# SoC_SDIO.net
KiCad netlist of a schematic drawn in Altium Designer
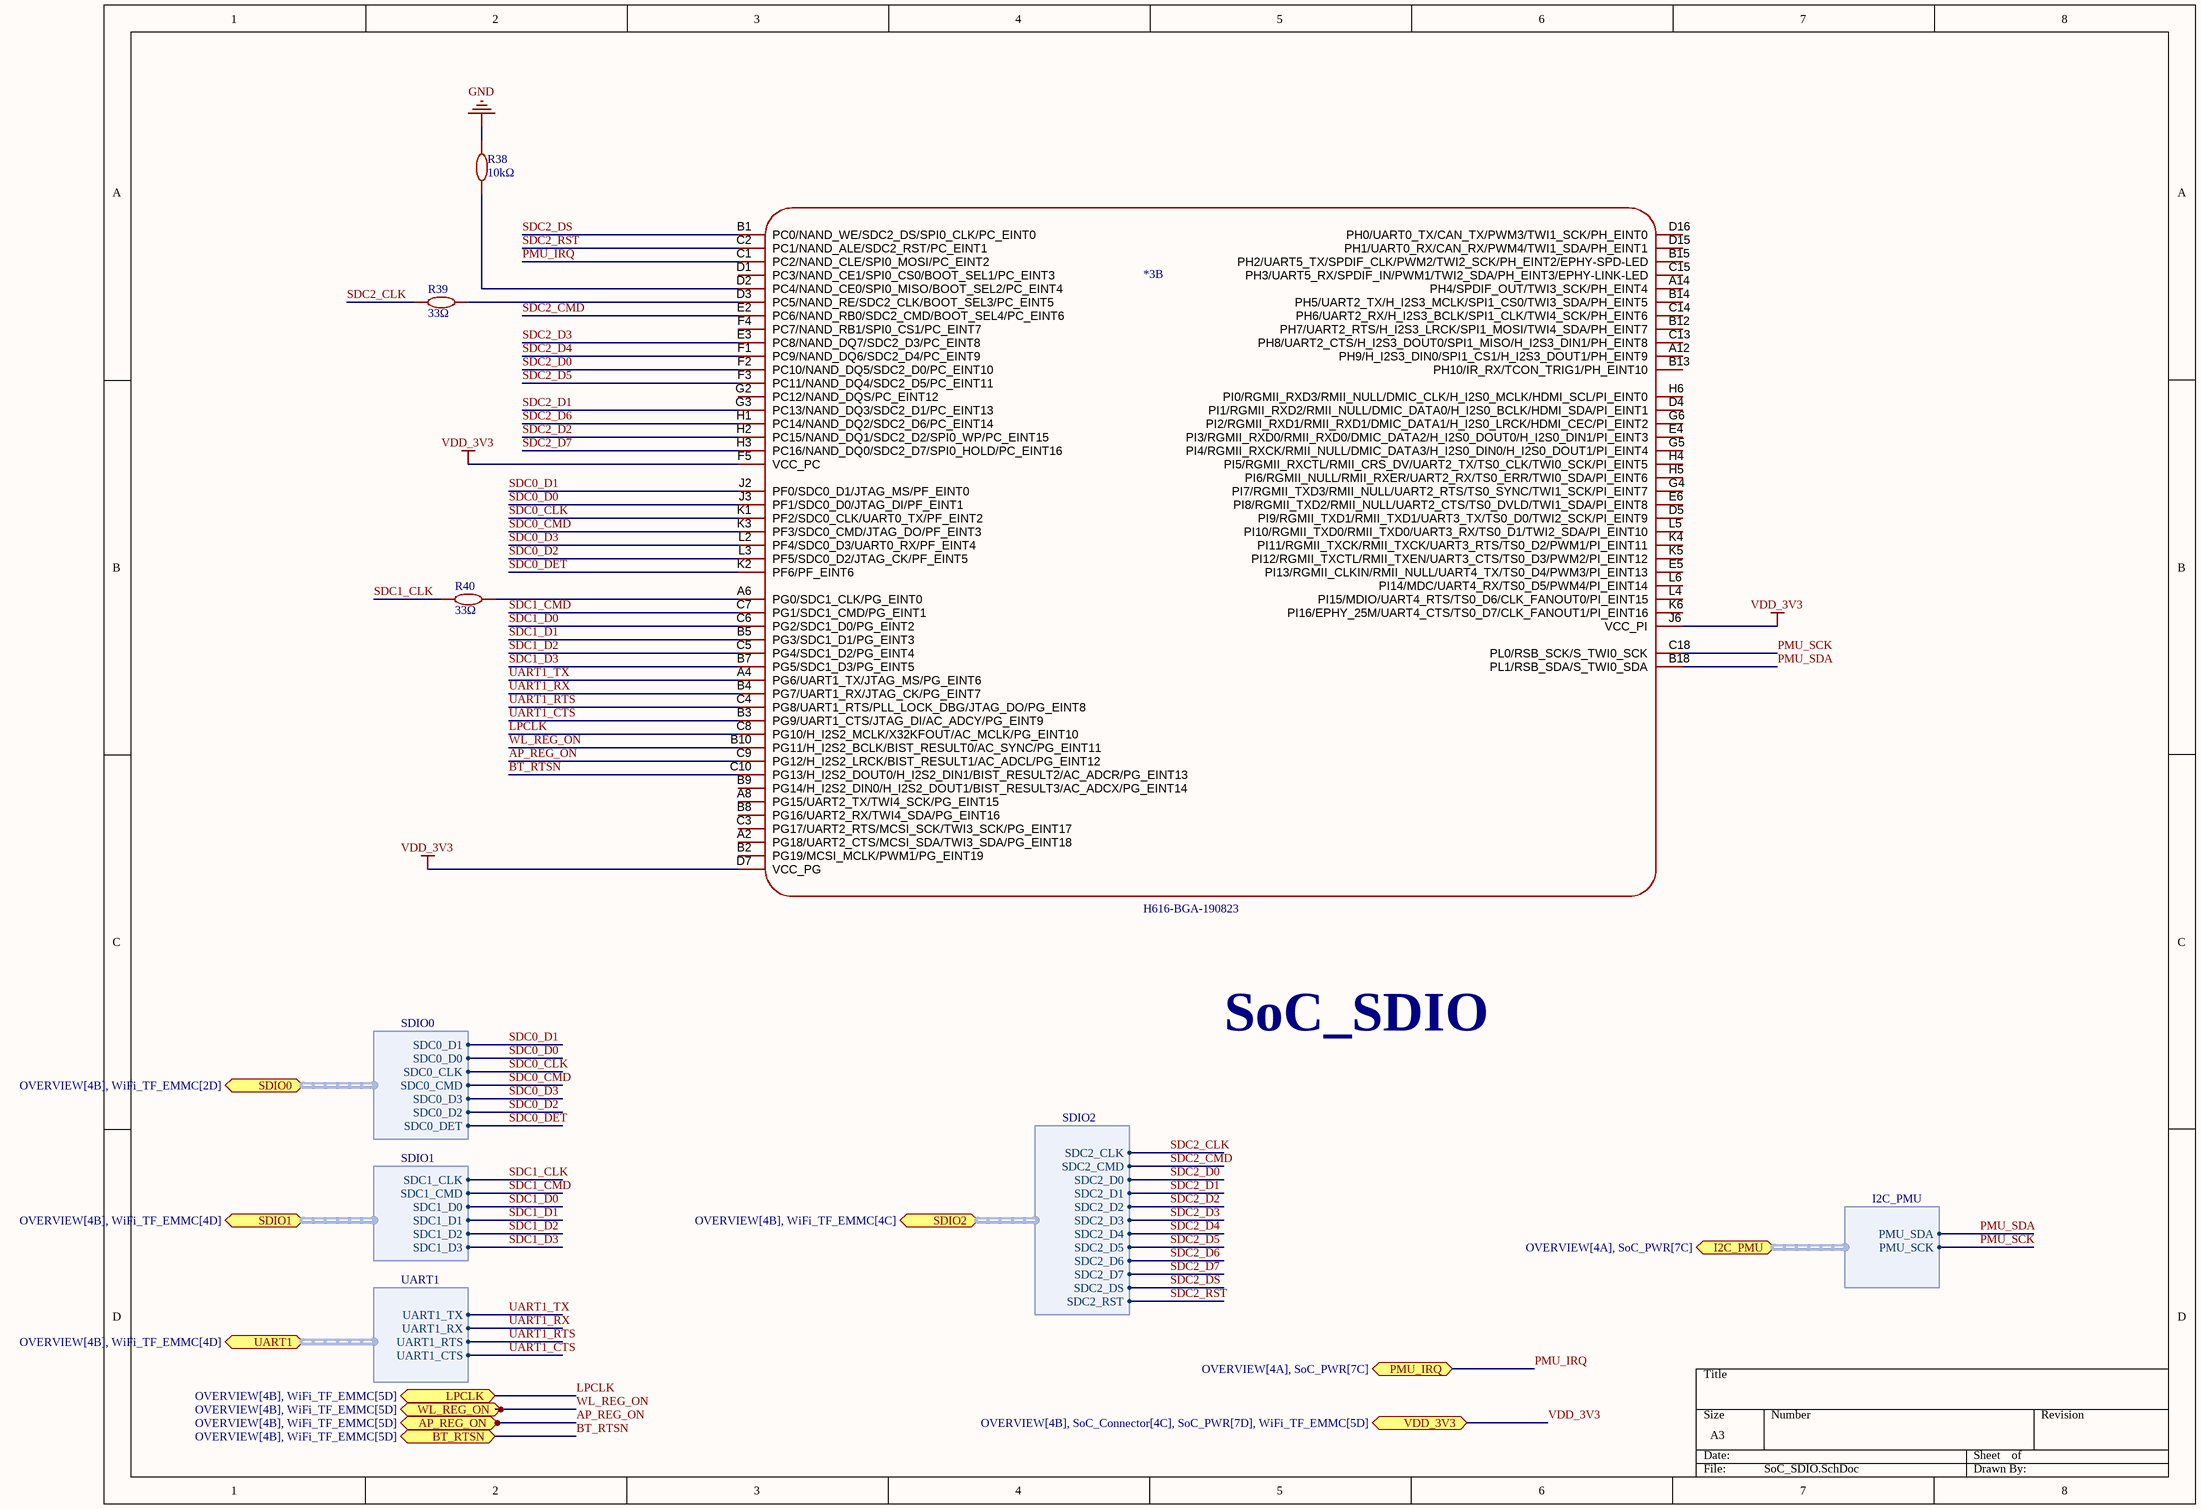
[diagram p0: SoC_SDIO.SchDoc]

(export (version "E")
  (design (tool "Eeschema 10.0.6"))
  (components
    (comp (ref "*3")
      (value "H616-BGA-190823")
      (footprint "BGA-284_L14.0-W12.0-P0.65-TL")
      (description "Allwinner H616")
      (libsource (lib "IC") (part "H616-BGA-190823"))
    )
    (comp (ref "R38")
      (value "10kΩ")
      (footprint "R0402")
      (description "62.5mW 10kΩ 50V ±100ppm/℃ Thick Film Resistor ±1% 0402 Chip Resistor - Surface Mount ROHS")
      (libsource (lib "RLC") (part "10kΩ"))
    )
    (comp (ref "R39")
      (value "33Ω")
      (footprint "R0402")
      (description "62.5mW 33Ω 50V ±100ppm/℃ Thick Film Resistor ±1% 0402 Chip Resistor - Surface Mount ROHS")
      (libsource (lib "RLC") (part "33Ω"))
    )
    (comp (ref "R40")
      (value "33Ω")
      (footprint "R0402")
      (description "62.5mW 33Ω 50V ±100ppm/℃ Thick Film Resistor ±1% 0402 Chip Resistor - Surface Mount ROHS")
      (libsource (lib "RLC") (part "33Ω"))
    )
  )
  (nets
    (net (code "6") (name "/AP_REG_ON") (class "Default")
      (node (ref "*3") (pin "C9") (pinfunction "PG12/H_I2S2_LRCK/BIST_RESULT1/AC_ADCL/PG_EINT12_C9") (pintype "passive"))
    )
    (net (code "7") (name "/BT_RTSN") (class "Default")
      (node (ref "*3") (pin "C10") (pinfunction "PG13/H_I2S2_DOUT0/H_I2S2_DIN1/BIST_RESULT2/AC_ADCR/PG_EINT13_C10") (pintype "passive"))
    )
    (net (code "8") (name "/LPCLK") (class "Default")
      (node (ref "*3") (pin "C8") (pinfunction "PG10/H_I2S2_MCLK/X32KFOUT/AC_MCLK/PG_EINT10_C8") (pintype "passive"))
    )
    (net (code "9") (name "/PMU_IRQ") (class "Default")
      (node (ref "*3") (pin "C1") (pinfunction "PC2/NAND_CLE/SPI0_MOSI/PC_EINT2_C1") (pintype "passive"))
    )
    (net (code "10") (name "/PMU_SCK") (class "Default")
      (node (ref "*3") (pin "C18") (pinfunction "PL0/RSB_SCK/S_TWI0_SCK_C18") (pintype "passive"))
    )
    (net (code "11") (name "/PMU_SDA") (class "Default")
      (node (ref "*3") (pin "B18") (pinfunction "PL1/RSB_SDA/S_TWI0_SDA_B18") (pintype "passive"))
    )
    (net (code "12") (name "/SDC0_CLK") (class "Default")
      (node (ref "*3") (pin "K1") (pinfunction "PF2/SDC0_CLK/UART0_TX/PF_EINT2_K1") (pintype "passive"))
    )
    (net (code "13") (name "/SDC0_CMD") (class "Default")
      (node (ref "*3") (pin "K3") (pinfunction "PF3/SDC0_CMD/JTAG_DO/PF_EINT3_K3") (pintype "passive"))
    )
    (net (code "14") (name "/SDC0_D0") (class "Default")
      (node (ref "*3") (pin "J3") (pinfunction "PF1/SDC0_D0/JTAG_DI/PF_EINT1_J3") (pintype "passive"))
    )
    (net (code "15") (name "/SDC0_D1") (class "Default")
      (node (ref "*3") (pin "J2") (pinfunction "PF0/SDC0_D1/JTAG_MS/PF_EINT0_J2") (pintype "passive"))
    )
    (net (code "16") (name "/SDC0_D2") (class "Default")
      (node (ref "*3") (pin "L3") (pinfunction "PF5/SDC0_D2/JTAG_CK/PF_EINT5_L3") (pintype "passive"))
    )
    (net (code "17") (name "/SDC0_D3") (class "Default")
      (node (ref "*3") (pin "L2") (pinfunction "PF4/SDC0_D3/UART0_RX/PF_EINT4_L2") (pintype "passive"))
    )
    (net (code "18") (name "/SDC0_DET") (class "Default")
      (node (ref "*3") (pin "K2") (pinfunction "PF6/PF_EINT6_K2") (pintype "passive"))
    )
    (net (code "19") (name "/SDC1_CLK") (class "Default")
      (node (ref "R40") (pin "1") (pinfunction "1_1") (pintype "passive"))
    )
    (net (code "20") (name "/SDC1_CMD") (class "Default")
      (node (ref "*3") (pin "C7") (pinfunction "PG1/SDC1_CMD/PG_EINT1_C7") (pintype "passive"))
    )
    (net (code "21") (name "/SDC1_D0") (class "Default")
      (node (ref "*3") (pin "C6") (pinfunction "PG2/SDC1_D0/PG_EINT2_C6") (pintype "passive"))
    )
    (net (code "22") (name "/SDC1_D1") (class "Default")
      (node (ref "*3") (pin "B5") (pinfunction "PG3/SDC1_D1/PG_EINT3_B5") (pintype "passive"))
    )
    (net (code "23") (name "/SDC1_D2") (class "Default")
      (node (ref "*3") (pin "C5") (pinfunction "PG4/SDC1_D2/PG_EINT4_C5") (pintype "passive"))
    )
    (net (code "24") (name "/SDC1_D3") (class "Default")
      (node (ref "*3") (pin "B7") (pinfunction "PG5/SDC1_D3/PG_EINT5_B7") (pintype "passive"))
    )
    (net (code "25") (name "/SDC2_CLK") (class "Default")
      (node (ref "R39") (pin "1") (pinfunction "1_1") (pintype "passive"))
    )
    (net (code "26") (name "/SDC2_CMD") (class "Default")
      (node (ref "*3") (pin "E2") (pinfunction "PC6/NAND_RB0/SDC2_CMD/BOOT_SEL4/PC_EINT6_E2") (pintype "passive"))
    )
    (net (code "27") (name "/SDC2_D0") (class "Default")
      (node (ref "*3") (pin "F2") (pinfunction "PC10/NAND_DQ5/SDC2_D0/PC_EINT10_F2") (pintype "passive"))
    )
    (net (code "28") (name "/SDC2_D1") (class "Default")
      (node (ref "*3") (pin "G3") (pinfunction "PC13/NAND_DQ3/SDC2_D1/PC_EINT13_G3") (pintype "passive"))
    )
    (net (code "29") (name "/SDC2_D2") (class "Default")
      (node (ref "*3") (pin "H2") (pinfunction "PC15/NAND_DQ1/SDC2_D2/SPI0_WP/PC_EINT15_H2") (pintype "passive"))
    )
    (net (code "30") (name "/SDC2_D3") (class "Default")
      (node (ref "*3") (pin "E3") (pinfunction "PC8/NAND_DQ7/SDC2_D3/PC_EINT8_E3") (pintype "passive"))
    )
    (net (code "31") (name "/SDC2_D4") (class "Default")
      (node (ref "*3") (pin "F1") (pinfunction "PC9/NAND_DQ6/SDC2_D4/PC_EINT9_F1") (pintype "passive"))
    )
    (net (code "32") (name "/SDC2_D5") (class "Default")
      (node (ref "*3") (pin "F3") (pinfunction "PC11/NAND_DQ4/SDC2_D5/PC_EINT11_F3") (pintype "passive"))
    )
    (net (code "33") (name "/SDC2_D6") (class "Default")
      (node (ref "*3") (pin "H1") (pinfunction "PC14/NAND_DQ2/SDC2_D6/PC_EINT14_H1") (pintype "passive"))
    )
    (net (code "34") (name "/SDC2_D7") (class "Default")
      (node (ref "*3") (pin "H3") (pinfunction "PC16/NAND_DQ0/SDC2_D7/SPI0_HOLD/PC_EINT16_H3") (pintype "passive"))
    )
    (net (code "35") (name "/SDC2_DS") (class "Default")
      (node (ref "*3") (pin "B1") (pinfunction "PC0/NAND_WE/SDC2_DS/SPI0_CLK/PC_EINT0_B1") (pintype "passive"))
    )
    (net (code "36") (name "/SDC2_RST") (class "Default")
      (node (ref "*3") (pin "C2") (pinfunction "PC1/NAND_ALE/SDC2_RST/PC_EINT1_C2") (pintype "passive"))
    )
    (net (code "37") (name "/UART1_CTS") (class "Default")
      (node (ref "*3") (pin "B3") (pinfunction "PG9/UART1_CTS/JTAG_DI/AC_ADCY/PG_EINT9_B3") (pintype "passive"))
    )
    (net (code "38") (name "/UART1_RTS") (class "Default")
      (node (ref "*3") (pin "C4") (pinfunction "PG8/UART1_RTS/PLL_LOCK_DBG/JTAG_DO/PG_EINT8_C4") (pintype "passive"))
    )
    (net (code "39") (name "/UART1_RX") (class "Default")
      (node (ref "*3") (pin "B4") (pinfunction "PG7/UART1_RX/JTAG_CK/PG_EINT7_B4") (pintype "passive"))
    )
    (net (code "40") (name "/UART1_TX") (class "Default")
      (node (ref "*3") (pin "A4") (pinfunction "PG6/UART1_TX/JTAG_MS/PG_EINT6_A4") (pintype "passive"))
    )
    (net (code "41") (name "/WL_REG_ON") (class "Default")
      (node (ref "*3") (pin "B10") (pinfunction "PG11/H_I2S2_BCLK/BIST_RESULT0/AC_SYNC/PG_EINT11_B10") (pintype "passive"))
    )
    (net (code "47") (name "GND") (class "Default")
      (node (ref "R38") (pin "2") (pinfunction "2_2") (pintype "passive"))
    )
    (net (code "48") (name "Net-(*3B-PC4{slash}NAND_CE0{slash}SPI0_MISO{slash}BOOT_SEL2{slash}PC_EINT4)") (class "Default")
      (node (ref "*3") (pin "D2") (pinfunction "PC4/NAND_CE0/SPI0_MISO/BOOT_SEL2/PC_EINT4_D2") (pintype "passive"))
      (node (ref "R38") (pin "1") (pinfunction "1_1") (pintype "passive"))
    )
    (net (code "49") (name "Net-(*3B-PC5{slash}NAND_RE{slash}SDC2_CLK{slash}BOOT_SEL3{slash}PC_EINT5)") (class "Default")
      (node (ref "*3") (pin "D3") (pinfunction "PC5/NAND_RE/SDC2_CLK/BOOT_SEL3/PC_EINT5_D3") (pintype "passive"))
      (node (ref "R39") (pin "2") (pinfunction "2_2") (pintype "passive"))
    )
    (net (code "50") (name "Net-(*3B-PG0{slash}SDC1_CLK{slash}PG_EINT0)") (class "Default")
      (node (ref "*3") (pin "A6") (pinfunction "PG0/SDC1_CLK/PG_EINT0_A6") (pintype "passive"))
      (node (ref "R40") (pin "2") (pinfunction "2_2") (pintype "passive"))
    )
    (net (code "51") (name "VDD_3V3") (class "Default")
      (node (ref "*3") (pin "D7") (pinfunction "VCC_PG_D7") (pintype "passive"))
      (node (ref "*3") (pin "F5") (pinfunction "VCC_PC_F5") (pintype "passive"))
      (node (ref "*3") (pin "J6") (pinfunction "VCC_PI_J6") (pintype "passive"))
    )
    (net (code "52") (name "unconnected-(*3B-PC3{slash}NAND_CE1{slash}SPI0_CS0{slash}BOOT_SEL1{slash}PC_EINT3-PadD1)") (class "Default")
      (node (ref "*3") (pin "D1") (pinfunction "PC3/NAND_CE1/SPI0_CS0/BOOT_SEL1/PC_EINT3_D1") (pintype "passive"))
    )
    (net (code "53") (name "unconnected-(*3B-PC7{slash}NAND_RB1{slash}SPI0_CS1{slash}PC_EINT7-PadF4)") (class "Default")
      (node (ref "*3") (pin "F4") (pinfunction "PC7/NAND_RB1/SPI0_CS1/PC_EINT7_F4") (pintype "passive"))
    )
    (net (code "54") (name "unconnected-(*3B-PC12{slash}NAND_DQS{slash}PC_EINT12-PadG2)") (class "Default")
      (node (ref "*3") (pin "G2") (pinfunction "PC12/NAND_DQS/PC_EINT12_G2") (pintype "passive"))
    )
    (net (code "55") (name "unconnected-(*3B-PG14{slash}H_I2S2_DIN0{slash}H_I2S2_DOUT1{slash}BIST_RESULT3{slash}AC_ADCX{slash}PG_EINT14-PadB9)") (class "Default")
      (node (ref "*3") (pin "B9") (pinfunction "PG14/H_I2S2_DIN0/H_I2S2_DOUT1/BIST_RESULT3/AC_ADCX/PG_EINT14_B9") (pintype "passive"))
    )
    (net (code "56") (name "unconnected-(*3B-PG15{slash}UART2_TX{slash}TWI4_SCK{slash}PG_EINT15-PadA8)") (class "Default")
      (node (ref "*3") (pin "A8") (pinfunction "PG15/UART2_TX/TWI4_SCK/PG_EINT15_A8") (pintype "passive"))
    )
    (net (code "57") (name "unconnected-(*3B-PG16{slash}UART2_RX{slash}TWI4_SDA{slash}PG_EINT16-PadB8)") (class "Default")
      (node (ref "*3") (pin "B8") (pinfunction "PG16/UART2_RX/TWI4_SDA/PG_EINT16_B8") (pintype "passive"))
    )
    (net (code "58") (name "unconnected-(*3B-PG17{slash}UART2_RTS{slash}MCSI_SCK{slash}TWI3_SCK{slash}PG_EINT17-PadC3)") (class "Default")
      (node (ref "*3") (pin "C3") (pinfunction "PG17/UART2_RTS/MCSI_SCK/TWI3_SCK/PG_EINT17_C3") (pintype "passive"))
    )
    (net (code "59") (name "unconnected-(*3B-PG18{slash}UART2_CTS{slash}MCSI_SDA{slash}TWI3_SDA{slash}PG_EINT18-PadA2)") (class "Default")
      (node (ref "*3") (pin "A2") (pinfunction "PG18/UART2_CTS/MCSI_SDA/TWI3_SDA/PG_EINT18_A2") (pintype "passive"))
    )
    (net (code "60") (name "unconnected-(*3B-PG19{slash}MCSI_MCLK{slash}PWM1{slash}PG_EINT19-PadB2)") (class "Default")
      (node (ref "*3") (pin "B2") (pinfunction "PG19/MCSI_MCLK/PWM1/PG_EINT19_B2") (pintype "passive"))
    )
    (net (code "61") (name "unconnected-(*3B-PH0{slash}UART0_TX{slash}CAN_TX{slash}PWM3{slash}TWI1_SCK{slash}PH_EINT0-PadD16)") (class "Default")
      (node (ref "*3") (pin "D16") (pinfunction "PH0/UART0_TX/CAN_TX/PWM3/TWI1_SCK/PH_EINT0_D16") (pintype "passive"))
    )
    (net (code "62") (name "unconnected-(*3B-PH1{slash}UART0_RX{slash}CAN_RX{slash}PWM4{slash}TWI1_SDA{slash}PH_EINT1-PadD15)") (class "Default")
      (node (ref "*3") (pin "D15") (pinfunction "PH1/UART0_RX/CAN_RX/PWM4/TWI1_SDA/PH_EINT1_D15") (pintype "passive"))
    )
    (net (code "63") (name "unconnected-(*3B-PH2{slash}UART5_TX{slash}SPDIF_CLK{slash}PWM2{slash}TWI2_SCK{slash}PH_EINT2{slash}EPHY-SPD-LED-PadB15)") (class "Default")
      (node (ref "*3") (pin "B15") (pinfunction "PH2/UART5_TX/SPDIF_CLK/PWM2/TWI2_SCK/PH_EINT2/EPHY-SPD-LED_B15") (pintype "passive"))
    )
    (net (code "64") (name "unconnected-(*3B-PH3{slash}UART5_RX{slash}SPDIF_IN{slash}PWM1{slash}TWI2_SDA{slash}PH_EINT3{slash}EPHY-LINK-LED-PadC15)") (class "Default")
      (node (ref "*3") (pin "C15") (pinfunction "PH3/UART5_RX/SPDIF_IN/PWM1/TWI2_SDA/PH_EINT3/EPHY-LINK-LED_C15") (pintype "passive"))
    )
    (net (code "65") (name "unconnected-(*3B-PH4{slash}SPDIF_OUT{slash}TWI3_SCK{slash}PH_EINT4-PadA14)") (class "Default")
      (node (ref "*3") (pin "A14") (pinfunction "PH4/SPDIF_OUT/TWI3_SCK/PH_EINT4_A14") (pintype "passive"))
    )
    (net (code "66") (name "unconnected-(*3B-PH5{slash}UART2_TX{slash}H_I2S3_MCLK{slash}SPI1_CS0{slash}TWI3_SDA{slash}PH_EINT5-PadB14)") (class "Default")
      (node (ref "*3") (pin "B14") (pinfunction "PH5/UART2_TX/H_I2S3_MCLK/SPI1_CS0/TWI3_SDA/PH_EINT5_B14") (pintype "passive"))
    )
    (net (code "67") (name "unconnected-(*3B-PH6{slash}UART2_RX{slash}H_I2S3_BCLK{slash}SPI1_CLK{slash}TWI4_SCK{slash}PH_EINT6-PadC14)") (class "Default")
      (node (ref "*3") (pin "C14") (pinfunction "PH6/UART2_RX/H_I2S3_BCLK/SPI1_CLK/TWI4_SCK/PH_EINT6_C14") (pintype "passive"))
    )
    (net (code "68") (name "unconnected-(*3B-PH7{slash}UART2_RTS{slash}H_I2S3_LRCK{slash}SPI1_MOSI{slash}TWI4_SDA{slash}PH_EINT7-PadB12)") (class "Default")
      (node (ref "*3") (pin "B12") (pinfunction "PH7/UART2_RTS/H_I2S3_LRCK/SPI1_MOSI/TWI4_SDA/PH_EINT7_B12") (pintype "passive"))
    )
    (net (code "69") (name "unconnected-(*3B-PH8{slash}UART2_CTS{slash}H_I2S3_DOUT0{slash}SPI1_MISO{slash}H_I2S3_DIN1{slash}PH_EINT8-PadC13)") (class "Default")
      (node (ref "*3") (pin "C13") (pinfunction "PH8/UART2_CTS/H_I2S3_DOUT0/SPI1_MISO/H_I2S3_DIN1/PH_EINT8_C13") (pintype "passive"))
    )
    (net (code "70") (name "unconnected-(*3B-PH9{slash}H_I2S3_DIN0{slash}SPI1_CS1{slash}H_I2S3_DOUT1{slash}PH_EINT9-PadA12)") (class "Default")
      (node (ref "*3") (pin "A12") (pinfunction "PH9/H_I2S3_DIN0/SPI1_CS1/H_I2S3_DOUT1/PH_EINT9_A12") (pintype "passive"))
    )
    (net (code "71") (name "unconnected-(*3B-PH10{slash}IR_RX{slash}TCON_TRIG1{slash}PH_EINT10-PadB13)") (class "Default")
      (node (ref "*3") (pin "B13") (pinfunction "PH10/IR_RX/TCON_TRIG1/PH_EINT10_B13") (pintype "passive"))
    )
    (net (code "72") (name "unconnected-(*3B-PI0{slash}RGMII_RXD3{slash}RMII_NULL{slash}DMIC_CLK{slash}H_I2S0_MCLK{slash}HDMI_SCL{slash}PI_EINT0-PadH6)") (class "Default")
      (node (ref "*3") (pin "H6") (pinfunction "PI0/RGMII_RXD3/RMII_NULL/DMIC_CLK/H_I2S0_MCLK/HDMI_SCL/PI_EINT0_H6") (pintype "passive"))
    )
    (net (code "73") (name "unconnected-(*3B-PI1{slash}RGMII_RXD2{slash}RMII_NULL{slash}DMIC_DATA0{slash}H_I2S0_BCLK{slash}HDMI_SDA{slash}PI_EINT1-PadD4)") (class "Default")
      (node (ref "*3") (pin "D4") (pinfunction "PI1/RGMII_RXD2/RMII_NULL/DMIC_DATA0/H_I2S0_BCLK/HDMI_SDA/PI_EINT1_D4") (pintype "passive"))
    )
    (net (code "74") (name "unconnected-(*3B-PI2{slash}RGMII_RXD1{slash}RMII_RXD1{slash}DMIC_DATA1{slash}H_I2S0_LRCK{slash}HDMI_CEC{slash}PI_EINT2-PadG6)") (class "Default")
      (node (ref "*3") (pin "G6") (pinfunction "PI2/RGMII_RXD1/RMII_RXD1/DMIC_DATA1/H_I2S0_LRCK/HDMI_CEC/PI_EINT2_G6") (pintype "passive"))
    )
    (net (code "75") (name "unconnected-(*3B-PI3{slash}RGMII_RXD0{slash}RMII_RXD0{slash}DMIC_DATA2{slash}H_I2S0_DOUT0{slash}H_I2S0_DIN1{slash}PI_EINT3-PadE4)") (class "Default")
      (node (ref "*3") (pin "E4") (pinfunction "PI3/RGMII_RXD0/RMII_RXD0/DMIC_DATA2/H_I2S0_DOUT0/H_I2S0_DIN1/PI_EINT3_E4") (pintype "passive"))
    )
    (net (code "76") (name "unconnected-(*3B-PI4{slash}RGMII_RXCK{slash}RMII_NULL{slash}DMIC_DATA3{slash}H_I2S0_DIN0{slash}H_I2S0_DOUT1{slash}PI_EINT4-PadG5)") (class "Default")
      (node (ref "*3") (pin "G5") (pinfunction "PI4/RGMII_RXCK/RMII_NULL/DMIC_DATA3/H_I2S0_DIN0/H_I2S0_DOUT1/PI_EINT4_G5") (pintype "passive"))
    )
    (net (code "77") (name "unconnected-(*3B-PI5{slash}RGMII_RXCTL{slash}RMII_CRS_DV{slash}UART2_TX{slash}TS0_CLK{slash}TWI0_SCK{slash}PI_EINT5-PadH4)") (class "Default")
      (node (ref "*3") (pin "H4") (pinfunction "PI5/RGMII_RXCTL/RMII_CRS_DV/UART2_TX/TS0_CLK/TWI0_SCK/PI_EINT5_H4") (pintype "passive"))
    )
    (net (code "78") (name "unconnected-(*3B-PI6{slash}RGMII_NULL{slash}RMII_RXER{slash}UART2_RX{slash}TS0_ERR{slash}TWI0_SDA{slash}PI_EINT6-PadH5)") (class "Default")
      (node (ref "*3") (pin "H5") (pinfunction "PI6/RGMII_NULL/RMII_RXER/UART2_RX/TS0_ERR/TWI0_SDA/PI_EINT6_H5") (pintype "passive"))
    )
    (net (code "79") (name "unconnected-(*3B-PI7{slash}RGMII_TXD3{slash}RMII_NULL{slash}UART2_RTS{slash}TS0_SYNC{slash}TWI1_SCK{slash}PI_EINT7-PadG4)") (class "Default")
      (node (ref "*3") (pin "G4") (pinfunction "PI7/RGMII_TXD3/RMII_NULL/UART2_RTS/TS0_SYNC/TWI1_SCK/PI_EINT7_G4") (pintype "passive"))
    )
    (net (code "80") (name "unconnected-(*3B-PI8{slash}RGMII_TXD2{slash}RMII_NULL{slash}UART2_CTS{slash}TS0_DVLD{slash}TWI1_SDA{slash}PI_EINT8-PadE6)") (class "Default")
      (node (ref "*3") (pin "E6") (pinfunction "PI8/RGMII_TXD2/RMII_NULL/UART2_CTS/TS0_DVLD/TWI1_SDA/PI_EINT8_E6") (pintype "passive"))
    )
    (net (code "81") (name "unconnected-(*3B-PI9{slash}RGMII_TXD1{slash}RMII_TXD1{slash}UART3_TX{slash}TS0_D0{slash}TWI2_SCK{slash}PI_EINT9-PadD5)") (class "Default")
      (node (ref "*3") (pin "D5") (pinfunction "PI9/RGMII_TXD1/RMII_TXD1/UART3_TX/TS0_D0/TWI2_SCK/PI_EINT9_D5") (pintype "passive"))
    )
    (net (code "82") (name "unconnected-(*3B-PI10{slash}RGMII_TXD0{slash}RMII_TXD0{slash}UART3_RX{slash}TS0_D1{slash}TWI2_SDA{slash}PI_EINT10-PadL5)") (class "Default")
      (node (ref "*3") (pin "L5") (pinfunction "PI10/RGMII_TXD0/RMII_TXD0/UART3_RX/TS0_D1/TWI2_SDA/PI_EINT10_L5") (pintype "passive"))
    )
    (net (code "83") (name "unconnected-(*3B-PI11{slash}RGMII_TXCK{slash}RMII_TXCK{slash}UART3_RTS{slash}TS0_D2{slash}PWM1{slash}PI_EINT11-PadK4)") (class "Default")
      (node (ref "*3") (pin "K4") (pinfunction "PI11/RGMII_TXCK/RMII_TXCK/UART3_RTS/TS0_D2/PWM1/PI_EINT11_K4") (pintype "passive"))
    )
    (net (code "84") (name "unconnected-(*3B-PI12{slash}RGMII_TXCTL{slash}RMII_TXEN{slash}UART3_CTS{slash}TS0_D3{slash}PWM2{slash}PI_EINT12-PadK5)") (class "Default")
      (node (ref "*3") (pin "K5") (pinfunction "PI12/RGMII_TXCTL/RMII_TXEN/UART3_CTS/TS0_D3/PWM2/PI_EINT12_K5") (pintype "passive"))
    )
    (net (code "85") (name "unconnected-(*3B-PI13{slash}RGMII_CLKIN{slash}RMII_NULL{slash}UART4_TX{slash}TS0_D4{slash}PWM3{slash}PI_EINT13-PadE5)") (class "Default")
      (node (ref "*3") (pin "E5") (pinfunction "PI13/RGMII_CLKIN/RMII_NULL/UART4_TX/TS0_D4/PWM3/PI_EINT13_E5") (pintype "passive"))
    )
    (net (code "86") (name "unconnected-(*3B-PI14{slash}MDC{slash}UART4_RX{slash}TS0_D5{slash}PWM4{slash}PI_EINT14-PadL6)") (class "Default")
      (node (ref "*3") (pin "L6") (pinfunction "PI14/MDC/UART4_RX/TS0_D5/PWM4/PI_EINT14_L6") (pintype "passive"))
    )
    (net (code "87") (name "unconnected-(*3B-PI15{slash}MDIO{slash}UART4_RTS{slash}TS0_D6{slash}CLK_FANOUT0{slash}PI_EINT15-PadL4)") (class "Default")
      (node (ref "*3") (pin "L4") (pinfunction "PI15/MDIO/UART4_RTS/TS0_D6/CLK_FANOUT0/PI_EINT15_L4") (pintype "passive"))
    )
    (net (code "88") (name "unconnected-(*3B-PI16{slash}EPHY_25M{slash}UART4_CTS{slash}TS0_D7{slash}CLK_FANOUT1{slash}PI_EINT16-PadK6)") (class "Default")
      (node (ref "*3") (pin "K6") (pinfunction "PI16/EPHY_25M/UART4_CTS/TS0_D7/CLK_FANOUT1/PI_EINT16_K6") (pintype "passive"))
    )
  )
)
